# ISL6236A_DEMO.net
KiCad netlist of a schematic drawn in Altium Designer
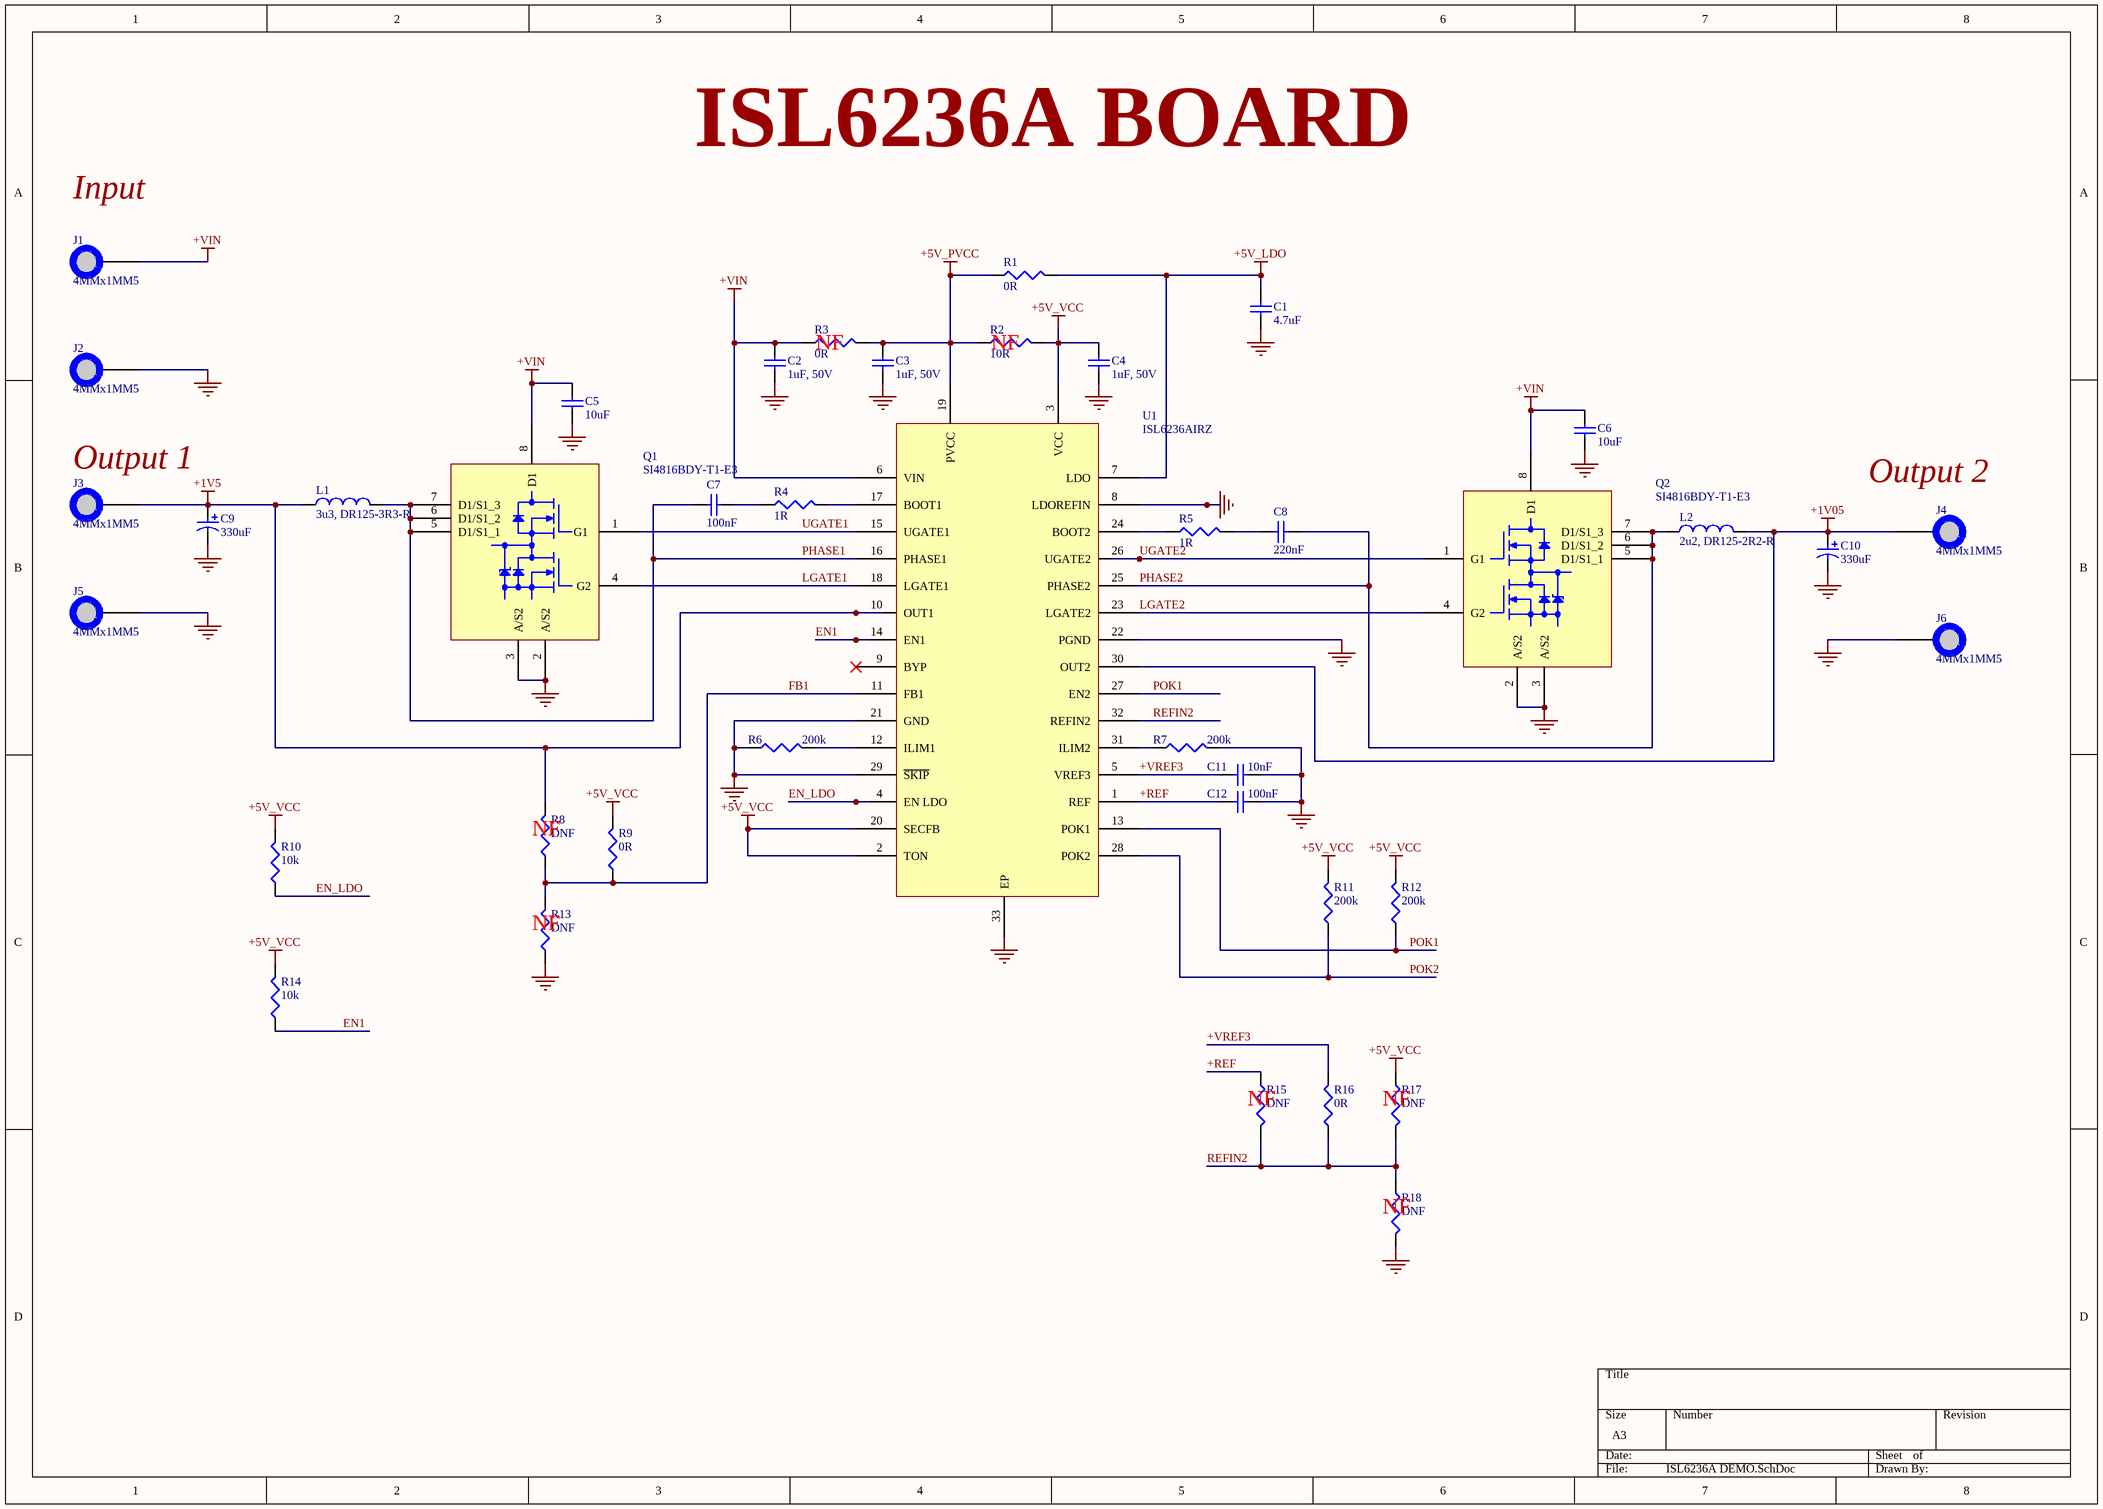
[diagram p0: ISL6236A DEMO.SchDoc]

(export (version "E")
  (design (tool "Eeschema 10.0.6"))
  (components
    (comp (ref "C1")
      (value "4.7uF")
      (footprint "C1206")
      (description "CAP CER 4.7UF 50V X5R 1206")
      (fields (field (name "TOLERANCE") "10%"))
      (libsource (lib "ISL6236A DEMO") (part "C3216X5R1H475K160AB"))
    )
    (comp (ref "C2")
      (value "1uF, 50V")
      (footprint "C0805")
      (description "Cap Ceramic 1uF 50V X7R 10% Pad SMD 0805 125°C T/R")
      (fields (field (name "TOLERANCE") "10%") (field (name "VOLTAGE") "50V"))
      (libsource (lib "ISL6236A DEMO") (part "C0805C105K5RACTU"))
    )
    (comp (ref "C3")
      (value "1uF, 50V")
      (footprint "C0805")
      (description "Cap Ceramic 1uF 50V X7R 10% Pad SMD 0805 125°C T/R")
      (fields (field (name "TOLERANCE") "10%") (field (name "VOLTAGE") "50V"))
      (libsource (lib "ISL6236A DEMO") (part "C0805C105K5RACTU"))
    )
    (comp (ref "C4")
      (value "1uF, 50V")
      (footprint "C0805")
      (description "Cap Ceramic 1uF 50V X7R 10% Pad SMD 0805 125°C T/R")
      (fields (field (name "TOLERANCE") "10%") (field (name "VOLTAGE") "50V"))
      (libsource (lib "ISL6236A DEMO") (part "C0805C105K5RACTU"))
    )
    (comp (ref "C5")
      (value "10uF")
      (footprint "C1210")
      (description "KEMET - C1210C106K6PACTU - CAP, MLCC, X5R, 10UF, 35V, 1210")
      (fields (field (name "VOLTAGE") "35V") (field (name "TOLERANCE") "10%"))
      (libsource (lib "ISL6236A DEMO") (part "C1210C106K6PACTU"))
    )
    (comp (ref "C6")
      (value "10uF")
      (footprint "C1210")
      (description "KEMET - C1210C106K6PACTU - CAP, MLCC, X5R, 10UF, 35V, 1210")
      (fields (field (name "VOLTAGE") "35V") (field (name "TOLERANCE") "10%"))
      (libsource (lib "ISL6236A DEMO") (part "C1210C106K6PACTU"))
    )
    (comp (ref "C7")
      (value "100nF")
      (footprint "C0805")
      (description "Cap Ceramic 0.1uF 50V X7R 10% SMD 2.0 x 1.2 mm 125 C Paper T/R")
      (fields (field (name "TOLERANCE") "10%") (field (name "VOLTAGE") "500V"))
      (libsource (lib "ISL6236A DEMO") (part "C0805C104K5RACTU"))
    )
    (comp (ref "C8")
      (value "220nF")
      (footprint "C0805")
      (description "CAP CER 0.22UF 50V X7R 0805")
      (fields (field (name "TOLERANCE") "10%") (field (name "VOLTAGE") "50V"))
      (libsource (lib "ISL6236A DEMO") (part "C0805C224K5RACTU"))
    )
    (comp (ref "C9")
      (value "330uF")
      (footprint "7343-43")
      (description "Tantalum Capacitors - Polymer SMD 330uF 10volts 20%")
      (fields (field (name "TOLERANCE") "20%") (field (name "VOLTAGE") "10V"))
      (libsource (lib "ISL6236A DEMO") (part "T530X337M010ATE004"))
    )
    (comp (ref "C10")
      (value "330uF")
      (footprint "7343-43")
      (description "Tantalum Capacitors - Polymer SMD 330uF 10volts 20%")
      (fields (field (name "TOLERANCE") "20%") (field (name "VOLTAGE") "10V"))
      (libsource (lib "ISL6236A DEMO") (part "T530X337M010ATE004"))
    )
    (comp (ref "C11")
      (value "10nF")
      (footprint "C0805")
      (description "CAP CER 10000PF 50V X7R 0805")
      (fields (field (name "TOLERANCE") "10%") (field (name "VOLTAGE") "50V"))
      (libsource (lib "ISL6236A DEMO") (part "C0805F103K5RACTU"))
    )
    (comp (ref "C12")
      (value "100nF")
      (footprint "C0805")
      (description "Cap Ceramic 0.1uF 50V X7R 10% SMD 2.0 x 1.2 mm 125 C Paper T/R")
      (fields (field (name "TOLERANCE") "10%") (field (name "VOLTAGE") "500V"))
      (libsource (lib "ISL6236A DEMO") (part "C0805C104K5RACTU"))
    )
    (comp (ref "J1")
      (value "4MMx1MM5")
      (footprint "PAD_WITH_HOLE_4MMx1MM5")
      (description "PAD_WITH_HOLE_4MMx1MM5")
      (libsource (lib "ISL6236A DEMO") (part "PAD_WITH_HOLE_4MMx1MM5"))
    )
    (comp (ref "J2")
      (value "4MMx1MM5")
      (footprint "PAD_WITH_HOLE_4MMx1MM5")
      (description "PAD_WITH_HOLE_4MMx1MM5")
      (libsource (lib "ISL6236A DEMO") (part "PAD_WITH_HOLE_4MMx1MM5"))
    )
    (comp (ref "J3")
      (value "4MMx1MM5")
      (footprint "PAD_WITH_HOLE_4MMx1MM5")
      (description "PAD_WITH_HOLE_4MMx1MM5")
      (libsource (lib "ISL6236A DEMO") (part "PAD_WITH_HOLE_4MMx1MM5"))
    )
    (comp (ref "J4")
      (value "4MMx1MM5")
      (footprint "PAD_WITH_HOLE_4MMx1MM5")
      (description "PAD_WITH_HOLE_4MMx1MM5")
      (libsource (lib "ISL6236A DEMO") (part "PAD_WITH_HOLE_4MMx1MM5"))
    )
    (comp (ref "J5")
      (value "4MMx1MM5")
      (footprint "PAD_WITH_HOLE_4MMx1MM5")
      (description "PAD_WITH_HOLE_4MMx1MM5")
      (libsource (lib "ISL6236A DEMO") (part "PAD_WITH_HOLE_4MMx1MM5"))
    )
    (comp (ref "J6")
      (value "4MMx1MM5")
      (footprint "PAD_WITH_HOLE_4MMx1MM5")
      (description "PAD_WITH_HOLE_4MMx1MM5")
      (libsource (lib "ISL6236A DEMO") (part "PAD_WITH_HOLE_4MMx1MM5"))
    )
    (comp (ref "L1")
      (value "3u3, DR125-3R3-R")
      (footprint "DR125")
      (description "FIXED IND 3.3UH 9.26A 6.3 MOHM")
      (fields (field (name "TOLERANCE") "20%"))
      (libsource (lib "ISL6236A DEMO") (part "DR125-3R3-R"))
    )
    (comp (ref "L2")
      (value "2u2, DR125-2R2-R")
      (footprint "DR125")
      (description "FIXED IND 2.2UH 10.9A 4.5 MOHM")
      (fields (field (name "TOLERANCE") "20%"))
      (libsource (lib "ISL6236A DEMO") (part "DR125-2R2-R"))
    )
    (comp (ref "Q1")
      (value "SI4816BDY-T1-E3")
      (footprint "SO-8")
      (description "MOSFET 2N-CH 30V 5.8A 8-SOIC")
      (libsource (lib "ISL6236A DEMO") (part "SI4816BDY-T1-E3"))
    )
    (comp (ref "Q2")
      (value "SI4816BDY-T1-E3")
      (footprint "SO-8")
      (description "MOSFET 2N-CH 30V 5.8A 8-SOIC")
      (libsource (lib "") (part "SI4816BDY-T1-E3_1"))
    )
    (comp (ref "R1")
      (value "0R")
      (footprint "R0805")
      (description "Thick Film Resistors - SMD 1/8W 0.0ohm 5%")
      (fields (field (name "TOLERANCE") "5%"))
      (libsource (lib "ISL6236A DEMO") (part "AC0805JR-070RL"))
    )
    (comp (ref "R2")
      (value "10R")
      (footprint "R0805")
      (description "Thick Film Resistors - SMD 1/8W 10ohm 1% AEC-Q200")
      (fields (field (name "TOLERANCE") "1%"))
      (libsource (lib "ISL6236A DEMO") (part "AC0805FR-0710RL"))
    )
    (comp (ref "R3")
      (value "0R")
      (footprint "R0805")
      (description "Thick Film Resistors - SMD 1/8W 0.0ohm 5%")
      (fields (field (name "TOLERANCE") "5%"))
      (libsource (lib "ISL6236A DEMO") (part "AC0805JR-070RL"))
    )
    (comp (ref "R4")
      (value "1R")
      (footprint "R0805")
      (description "AC Series 0805 0.125 W 1 Ohm ±1% ±200 ppm/°C SMT Thick Film Chip Resistor")
      (fields (field (name "TOLERANCE") "1%"))
      (libsource (lib "ISL6236A DEMO") (part "AC0805FR-071RL"))
    )
    (comp (ref "R5")
      (value "1R")
      (footprint "R0805")
      (description "AC Series 0805 0.125 W 1 Ohm ±1% ±200 ppm/°C SMT Thick Film Chip Resistor")
      (fields (field (name "TOLERANCE") "1%"))
      (libsource (lib "ISL6236A DEMO") (part "AC0805FR-071RL"))
    )
    (comp (ref "R6")
      (value "200k")
      (footprint "R0805")
      (description "Thick Film Resistors - SMD 1/8W 200K ohm 1% AEC-Q200")
      (fields (field (name "TOLERANCE") "1%"))
      (libsource (lib "ISL6236A DEMO") (part "AC0805FR-07200KL"))
    )
    (comp (ref "R7")
      (value "200k")
      (footprint "R0805")
      (description "Thick Film Resistors - SMD 1/8W 200K ohm 1% AEC-Q200")
      (fields (field (name "TOLERANCE") "1%"))
      (libsource (lib "ISL6236A DEMO") (part "AC0805FR-07200KL"))
    )
    (comp (ref "R8") (value "DNF") (footprint "R0805") (libsource (lib "ISL6236A DEMO") (part "RES")))
    (comp (ref "R9")
      (value "0R")
      (footprint "R0805")
      (description "Thick Film Resistors - SMD 1/8W 0.0ohm 5%")
      (fields (field (name "TOLERANCE") "5%"))
      (libsource (lib "ISL6236A DEMO") (part "AC0805JR-070RL"))
    )
    (comp (ref "R10")
      (value "10k")
      (footprint "R0805")
      (description "RES SMD 10K OHM 1% 1/8W 0805")
      (fields (field (name "TOLERANCE") "1%"))
      (libsource (lib "ISL6236A DEMO") (part "AC0805FR-0710KL"))
    )
    (comp (ref "R11")
      (value "200k")
      (footprint "R0805")
      (description "Thick Film Resistors - SMD 1/8W 200K ohm 1% AEC-Q200")
      (fields (field (name "TOLERANCE") "1%"))
      (libsource (lib "ISL6236A DEMO") (part "AC0805FR-07200KL"))
    )
    (comp (ref "R12")
      (value "200k")
      (footprint "R0805")
      (description "Thick Film Resistors - SMD 1/8W 200K ohm 1% AEC-Q200")
      (fields (field (name "TOLERANCE") "1%"))
      (libsource (lib "ISL6236A DEMO") (part "AC0805FR-07200KL"))
    )
    (comp (ref "R13") (value "DNF") (footprint "R0805") (libsource (lib "ISL6236A DEMO") (part "RES")))
    (comp (ref "R14")
      (value "10k")
      (footprint "R0805")
      (description "RES SMD 10K OHM 1% 1/8W 0805")
      (fields (field (name "TOLERANCE") "1%"))
      (libsource (lib "ISL6236A DEMO") (part "AC0805FR-0710KL"))
    )
    (comp (ref "R15") (value "DNF") (footprint "R0805") (libsource (lib "ISL6236A DEMO") (part "RES")))
    (comp (ref "R16")
      (value "0R")
      (footprint "R0805")
      (description "Thick Film Resistors - SMD 1/8W 0.0ohm 5%")
      (fields (field (name "TOLERANCE") "5%"))
      (libsource (lib "ISL6236A DEMO") (part "AC0805JR-070RL"))
    )
    (comp (ref "R17") (value "DNF") (footprint "R0805") (libsource (lib "ISL6236A DEMO") (part "RES")))
    (comp (ref "R18") (value "DNF") (footprint "R0805") (libsource (lib "ISL6236A DEMO") (part "RES")))
    (comp (ref "U1")
      (value "ISL6236AIRZ")
      (footprint "L32.5x5B")
      (description "IC MAIN PWR CTRLR QUAD 32-QFN")
      (libsource (lib "ISL6236A DEMO") (part "ISL6236AIRZ"))
    )
  )
  (nets
    (net (code "1") (name "+1V05") (class "Default")
      (node (ref "C10") (pin "1") (pinfunction "1_1") (pintype "passive"))
      (node (ref "J4") (pin "1") (pinfunction "1_1") (pintype "passive"))
      (node (ref "L2") (pin "2") (pinfunction "2_2") (pintype "passive"))
      (node (ref "U1") (pin "30") (pinfunction "OUT2_30") (pintype "passive"))
    )
    (net (code "2") (name "+1V5") (class "Default")
      (node (ref "C9") (pin "1") (pinfunction "1_1") (pintype "passive"))
      (node (ref "J3") (pin "1") (pinfunction "1_1") (pintype "passive"))
      (node (ref "L1") (pin "1") (pinfunction "1_1") (pintype "passive"))
      (node (ref "R8") (pin "2") (pinfunction "2_2") (pintype "passive"))
      (node (ref "U1") (pin "10") (pinfunction "OUT1_10") (pintype "passive"))
    )
    (net (code "3") (name "+5V_LDO") (class "Default")
      (node (ref "C1") (pin "1") (pinfunction "1_1") (pintype "passive"))
      (node (ref "R1") (pin "2") (pinfunction "2_2") (pintype "passive"))
      (node (ref "U1") (pin "7") (pinfunction "LDO_7") (pintype "passive"))
    )
    (net (code "4") (name "+5V_PVCC") (class "Default")
      (node (ref "C3") (pin "2") (pinfunction "2_2") (pintype "passive"))
      (node (ref "R1") (pin "1") (pinfunction "1_1") (pintype "passive"))
      (node (ref "R2") (pin "1") (pinfunction "1_1") (pintype "passive"))
      (node (ref "R3") (pin "2") (pinfunction "2_2") (pintype "passive"))
      (node (ref "U1") (pin "19") (pinfunction "PVCC_19") (pintype "passive"))
    )
    (net (code "5") (name "+5V_VCC") (class "Default")
      (node (ref "C4") (pin "2") (pinfunction "2_2") (pintype "passive"))
      (node (ref "R10") (pin "2") (pinfunction "2_2") (pintype "passive"))
      (node (ref "R11") (pin "2") (pinfunction "2_2") (pintype "passive"))
      (node (ref "R12") (pin "2") (pinfunction "2_2") (pintype "passive"))
      (node (ref "R14") (pin "2") (pinfunction "2_2") (pintype "passive"))
      (node (ref "R17") (pin "1") (pinfunction "1_1") (pintype "passive"))
      (node (ref "R2") (pin "2") (pinfunction "2_2") (pintype "passive"))
      (node (ref "R9") (pin "2") (pinfunction "2_2") (pintype "passive"))
      (node (ref "U1") (pin "2") (pinfunction "TON_2") (pintype "passive"))
      (node (ref "U1") (pin "20") (pinfunction "SECFB_20") (pintype "passive"))
      (node (ref "U1") (pin "3") (pinfunction "VCC_3") (pintype "passive"))
    )
    (net (code "6") (name "+VIN") (class "Default")
      (node (ref "C2") (pin "2") (pinfunction "2_2") (pintype "passive"))
      (node (ref "C5") (pin "2") (pinfunction "2_2") (pintype "passive"))
      (node (ref "C6") (pin "1") (pinfunction "1_1") (pintype "passive"))
      (node (ref "J1") (pin "1") (pinfunction "1_1") (pintype "passive"))
      (node (ref "Q1") (pin "8") (pinfunction "D1_8") (pintype "passive"))
      (node (ref "Q2") (pin "8") (pinfunction "D1_8") (pintype "passive"))
      (node (ref "R3") (pin "1") (pinfunction "1_1") (pintype "passive"))
      (node (ref "U1") (pin "6") (pinfunction "VIN_6") (pintype "passive"))
    )
    (net (code "7") (name "/+REF") (class "Default")
      (node (ref "C12") (pin "1") (pinfunction "1_1") (pintype "passive"))
      (node (ref "R15") (pin "1") (pinfunction "1_1") (pintype "passive"))
      (node (ref "U1") (pin "1") (pinfunction "REF_1") (pintype "passive"))
    )
    (net (code "8") (name "/+VREF3") (class "Default")
      (node (ref "C11") (pin "1") (pinfunction "1_1") (pintype "passive"))
      (node (ref "R16") (pin "2") (pinfunction "2_2") (pintype "passive"))
      (node (ref "U1") (pin "5") (pinfunction "VREF3_5") (pintype "passive"))
    )
    (net (code "9") (name "/EN1") (class "Default")
      (node (ref "R14") (pin "1") (pinfunction "1_1") (pintype "passive"))
      (node (ref "U1") (pin "14") (pinfunction "EN1_14") (pintype "passive"))
    )
    (net (code "10") (name "/EN_LDO") (class "Default")
      (node (ref "R10") (pin "1") (pinfunction "1_1") (pintype "passive"))
      (node (ref "U1") (pin "4") (pinfunction "EN_LDO_4") (pintype "passive"))
    )
    (net (code "11") (name "/FB1") (class "Default")
      (node (ref "R13") (pin "2") (pinfunction "2_2") (pintype "passive"))
      (node (ref "R8") (pin "1") (pinfunction "1_1") (pintype "passive"))
      (node (ref "R9") (pin "1") (pinfunction "1_1") (pintype "passive"))
      (node (ref "U1") (pin "11") (pinfunction "FB1_11") (pintype "passive"))
    )
    (net (code "12") (name "/LGATE1") (class "Default")
      (node (ref "Q1") (pin "4") (pinfunction "G2_4") (pintype "passive"))
      (node (ref "U1") (pin "18") (pinfunction "LGATE1_18") (pintype "passive"))
    )
    (net (code "13") (name "/LGATE2") (class "Default")
      (node (ref "Q2") (pin "4") (pinfunction "G2_4") (pintype "passive"))
      (node (ref "U1") (pin "23") (pinfunction "LGATE2_23") (pintype "passive"))
    )
    (net (code "14") (name "/PHASE1") (class "Default")
      (node (ref "C7") (pin "1") (pinfunction "1_1") (pintype "passive"))
      (node (ref "L1") (pin "2") (pinfunction "2_2") (pintype "passive"))
      (node (ref "Q1") (pin "5") (pinfunction "D1/S1_1_5") (pintype "passive"))
      (node (ref "Q1") (pin "6") (pinfunction "D1/S1_2_6") (pintype "passive"))
      (node (ref "Q1") (pin "7") (pinfunction "D1/S1_3_7") (pintype "passive"))
      (node (ref "U1") (pin "16") (pinfunction "PHASE1_16") (pintype "passive"))
    )
    (net (code "15") (name "/PHASE2") (class "Default")
      (node (ref "C8") (pin "2") (pinfunction "2_2") (pintype "passive"))
      (node (ref "L2") (pin "1") (pinfunction "1_1") (pintype "passive"))
      (node (ref "Q2") (pin "5") (pinfunction "D1/S1_1_5") (pintype "passive"))
      (node (ref "Q2") (pin "6") (pinfunction "D1/S1_2_6") (pintype "passive"))
      (node (ref "Q2") (pin "7") (pinfunction "D1/S1_3_7") (pintype "passive"))
      (node (ref "U1") (pin "25") (pinfunction "PHASE2_25") (pintype "passive"))
    )
    (net (code "16") (name "/POK1") (class "Default")
      (node (ref "R12") (pin "1") (pinfunction "1_1") (pintype "passive"))
      (node (ref "U1") (pin "13") (pinfunction "POK1_13") (pintype "passive"))
      (node (ref "U1") (pin "27") (pinfunction "EN2_27") (pintype "passive"))
    )
    (net (code "17") (name "/POK2") (class "Default")
      (node (ref "R11") (pin "1") (pinfunction "1_1") (pintype "passive"))
      (node (ref "U1") (pin "28") (pinfunction "POK2_28") (pintype "passive"))
    )
    (net (code "18") (name "/REFIN2") (class "Default")
      (node (ref "R15") (pin "2") (pinfunction "2_2") (pintype "passive"))
      (node (ref "R16") (pin "1") (pinfunction "1_1") (pintype "passive"))
      (node (ref "R17") (pin "2") (pinfunction "2_2") (pintype "passive"))
      (node (ref "R18") (pin "1") (pinfunction "1_1") (pintype "passive"))
      (node (ref "U1") (pin "32") (pinfunction "REFIN2_32") (pintype "passive"))
    )
    (net (code "19") (name "/UGATE1") (class "Default")
      (node (ref "Q1") (pin "1") (pinfunction "G1_1") (pintype "passive"))
      (node (ref "U1") (pin "15") (pinfunction "UGATE1_15") (pintype "passive"))
    )
    (net (code "20") (name "/UGATE2") (class "Default")
      (node (ref "Q2") (pin "1") (pinfunction "G1_1") (pintype "passive"))
      (node (ref "U1") (pin "26") (pinfunction "UGATE2_26") (pintype "passive"))
    )
    (net (code "21") (name "GND") (class "Default")
      (node (ref "C1") (pin "2") (pinfunction "2_2") (pintype "passive"))
      (node (ref "C10") (pin "2") (pinfunction "2_2") (pintype "passive"))
      (node (ref "C11") (pin "2") (pinfunction "2_2") (pintype "passive"))
      (node (ref "C12") (pin "2") (pinfunction "2_2") (pintype "passive"))
      (node (ref "C2") (pin "1") (pinfunction "1_1") (pintype "passive"))
      (node (ref "C3") (pin "1") (pinfunction "1_1") (pintype "passive"))
      (node (ref "C4") (pin "1") (pinfunction "1_1") (pintype "passive"))
      (node (ref "C5") (pin "1") (pinfunction "1_1") (pintype "passive"))
      (node (ref "C6") (pin "2") (pinfunction "2_2") (pintype "passive"))
      (node (ref "C9") (pin "2") (pinfunction "2_2") (pintype "passive"))
      (node (ref "J2") (pin "1") (pinfunction "1_1") (pintype "passive"))
      (node (ref "J5") (pin "1") (pinfunction "1_1") (pintype "passive"))
      (node (ref "J6") (pin "1") (pinfunction "1_1") (pintype "passive"))
      (node (ref "Q1") (pin "2") (pinfunction "A/S2_2") (pintype "passive"))
      (node (ref "Q1") (pin "3") (pinfunction "A/S2_3") (pintype "passive"))
      (node (ref "Q2") (pin "2") (pinfunction "A/S2_2") (pintype "passive"))
      (node (ref "Q2") (pin "3") (pinfunction "A/S2_3") (pintype "passive"))
      (node (ref "R13") (pin "1") (pinfunction "1_1") (pintype "passive"))
      (node (ref "R18") (pin "2") (pinfunction "2_2") (pintype "passive"))
      (node (ref "R6") (pin "1") (pinfunction "1_1") (pintype "passive"))
      (node (ref "R7") (pin "2") (pinfunction "2_2") (pintype "passive"))
      (node (ref "U1") (pin "21") (pinfunction "GND_21") (pintype "passive"))
      (node (ref "U1") (pin "22") (pinfunction "PGND_22") (pintype "passive"))
      (node (ref "U1") (pin "29") (pinfunction "~{SKIP}_29") (pintype "passive"))
      (node (ref "U1") (pin "33") (pinfunction "EP_33") (pintype "passive"))
      (node (ref "U1") (pin "8") (pinfunction "LDOREFIN_8") (pintype "passive"))
    )
    (net (code "22") (name "Net-(C7-Pad2)") (class "Default")
      (node (ref "C7") (pin "2") (pinfunction "2_2") (pintype "passive"))
      (node (ref "R4") (pin "1") (pinfunction "1_1") (pintype "passive"))
    )
    (net (code "23") (name "Net-(C8-Pad1)") (class "Default")
      (node (ref "C8") (pin "1") (pinfunction "1_1") (pintype "passive"))
      (node (ref "R5") (pin "2") (pinfunction "2_2") (pintype "passive"))
    )
    (net (code "24") (name "Net-(U1-BOOT1)") (class "Default")
      (node (ref "R4") (pin "2") (pinfunction "2_2") (pintype "passive"))
      (node (ref "U1") (pin "17") (pinfunction "BOOT1_17") (pintype "passive"))
    )
    (net (code "25") (name "Net-(U1-BOOT2)") (class "Default")
      (node (ref "R5") (pin "1") (pinfunction "1_1") (pintype "passive"))
      (node (ref "U1") (pin "24") (pinfunction "BOOT2_24") (pintype "passive"))
    )
    (net (code "26") (name "Net-(U1-ILIM1)") (class "Default")
      (node (ref "R6") (pin "2") (pinfunction "2_2") (pintype "passive"))
      (node (ref "U1") (pin "12") (pinfunction "ILIM1_12") (pintype "passive"))
    )
    (net (code "27") (name "Net-(U1-ILIM2)") (class "Default")
      (node (ref "R7") (pin "1") (pinfunction "1_1") (pintype "passive"))
      (node (ref "U1") (pin "31") (pinfunction "ILIM2_31") (pintype "passive"))
    )
    (net (code "28") (name "unconnected-(U1-BYP-Pad9)") (class "Default")
      (node (ref "U1") (pin "9") (pinfunction "BYP_9") (pintype "passive+no_connect"))
    )
  )
)
